# relay.net
KiCad netlist of a schematic drawn in Altium Designer
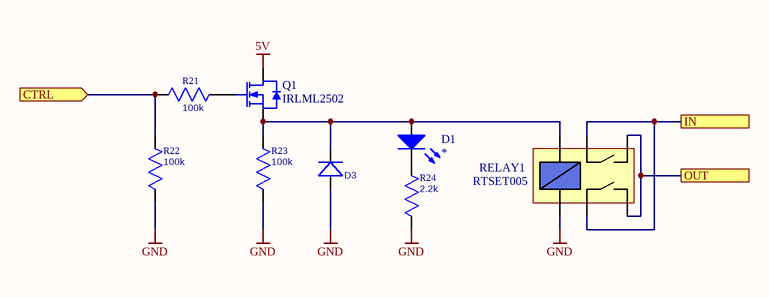
[diagram p0: relay.SchDoc]

(export (version "E")
  (design (tool "Eeschema 10.0.6"))
  (components
    (comp (ref "D1")
      (value "*")
      (footprint "LED_5mm")
      (description "Typical INFRARED GaAs LED")
      (libsource (lib "AX_Altium_v2.3") (part "LED_5mm"))
    )
    (comp (ref "D3")
      (value "D_DO-214AC")
      (footprint "DO-214AC")
      (description "Diode")
      (libsource (lib "AX_Altium_v2.3") (part "D_DO-214AC"))
    )
    (comp (ref "Q1")
      (value "IRLML2502")
      (footprint "SOT23")
      (description "N-Channel Enhancement Mode MOSFET")
      (fields (field (name "PUBLISHER") "Altium Limited"))
      (libsource (lib "AX_Altium_v2.3") (part "N-ch_SOT23"))
    )
    (comp (ref "R21")
      (value "100k")
      (footprint "R_0603")
      (description "Resistor")
      (libsource (lib "AX_Altium_v2.3") (part "R0603"))
    )
    (comp (ref "R22")
      (value "100k")
      (footprint "R_0603")
      (description "Resistor")
      (libsource (lib "AX_Altium_v2.3") (part "R0603"))
    )
    (comp (ref "R23")
      (value "100k")
      (footprint "R_0603")
      (description "Resistor")
      (libsource (lib "AX_Altium_v2.3") (part "R0603"))
    )
    (comp (ref "R24")
      (value "2.2k")
      (footprint "R_0603")
      (description "Resistor")
      (libsource (lib "AX_Altium_v2.3") (part "R0603"))
    )
    (comp (ref "RELAY1")
      (value "RTSET005")
      (footprint "RTSET005")
      (description "General Purpose Relay")
      (libsource (lib "SmartOutletIntegratedLibrary") (part "1-1415898-8"))
    )
  )
  (nets
    (net (code "1") (name "/CTRL") (class "Default")
      (node (ref "R21") (pin "2") (pintype "passive"))
      (node (ref "R22") (pin "1") (pintype "passive"))
    )
    (net (code "2") (name "/IN") (class "Default")
      (node (ref "RELAY1") (pin "3") (pinfunction "3_3") (pintype "passive"))
      (node (ref "RELAY1") (pin "4") (pinfunction "4_4") (pintype "passive"))
    )
    (net (code "3") (name "/OUT") (class "Default")
      (node (ref "RELAY1") (pin "1") (pinfunction "1_1") (pintype "passive"))
      (node (ref "RELAY1") (pin "2") (pinfunction "2_2") (pintype "passive"))
    )
    (net (code "4") (name "5V") (class "Default")
      (node (ref "Q1") (pin "3") (pinfunction "D_3") (pintype "passive"))
    )
    (net (code "5") (name "GND") (class "Default")
      (node (ref "D3") (pin "1") (pinfunction "A_1") (pintype "passive"))
      (node (ref "R22") (pin "2") (pintype "passive"))
      (node (ref "R23") (pin "2") (pintype "passive"))
      (node (ref "R24") (pin "1") (pintype "passive"))
      (node (ref "RELAY1") (pin "6") (pinfunction "6_6") (pintype "passive"))
    )
    (net (code "6") (name "Net-(D1-A)") (class "Default")
      (node (ref "D1") (pin "1") (pinfunction "A_1") (pintype "passive"))
      (node (ref "D3") (pin "2") (pinfunction "K_2") (pintype "passive"))
      (node (ref "Q1") (pin "2") (pinfunction "S_2") (pintype "passive"))
      (node (ref "R23") (pin "1") (pintype "passive"))
      (node (ref "RELAY1") (pin "5") (pinfunction "5_5") (pintype "passive"))
    )
    (net (code "7") (name "Net-(D1-K)") (class "Default")
      (node (ref "D1") (pin "2") (pinfunction "K_2") (pintype "passive"))
      (node (ref "R24") (pin "2") (pintype "passive"))
    )
    (net (code "8") (name "Net-(Q1-G)") (class "Default")
      (node (ref "Q1") (pin "1") (pinfunction "G_1") (pintype "passive"))
      (node (ref "R21") (pin "1") (pintype "passive"))
    )
  )
)
